# SolarPanelXPlus.net
KiCad netlist of a schematic drawn in Altium Designer
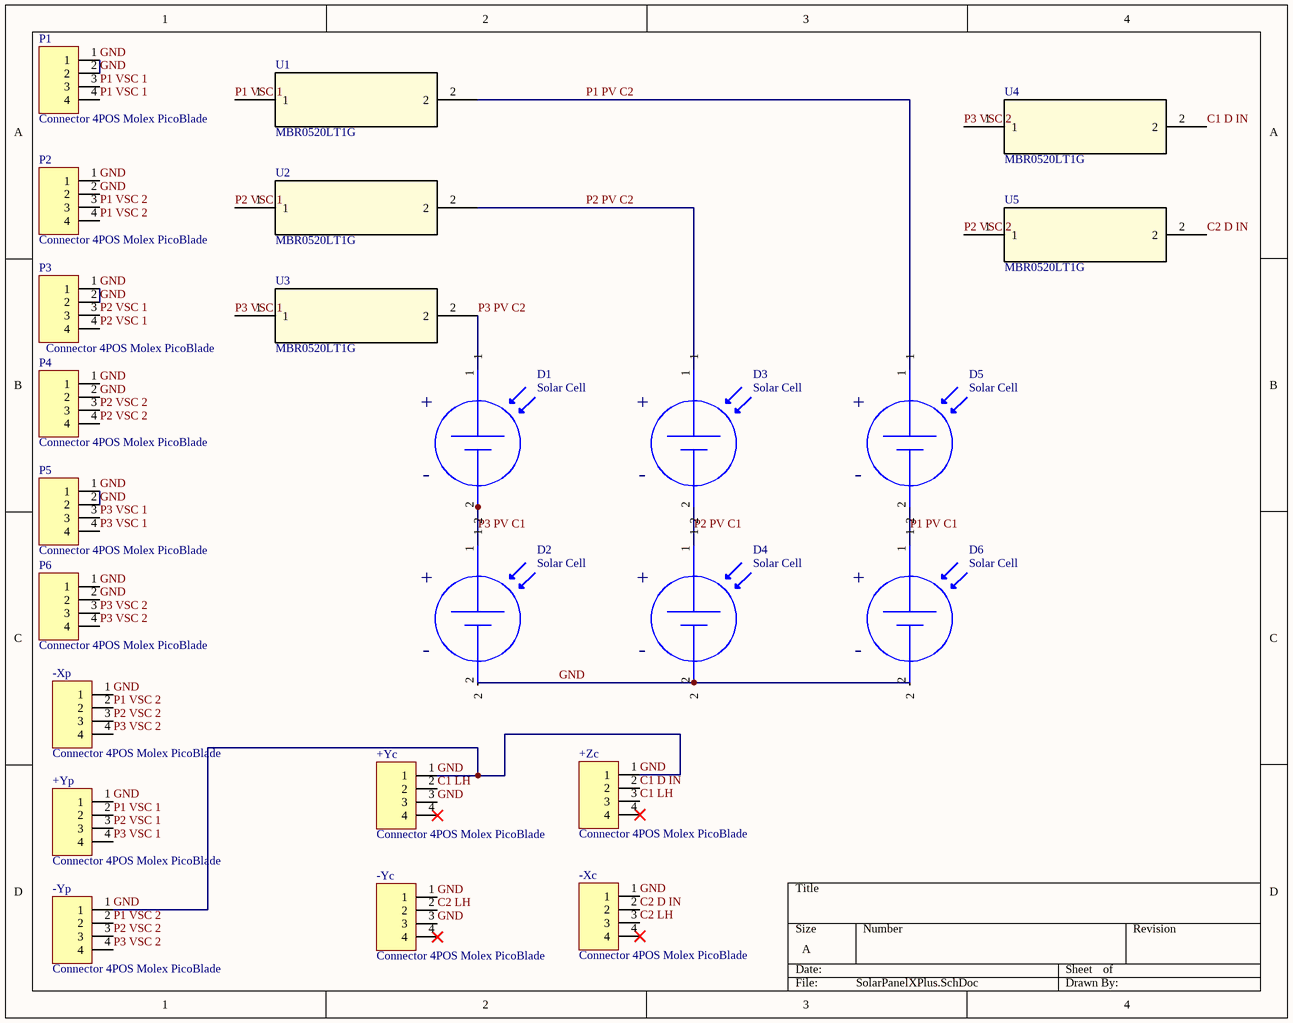
[diagram p0: SolarPanelXPlus.SchDoc]

(export (version "E")
  (design (tool "Eeschema 10.0.6"))
  (components
    (comp (ref "+Yc")
      (value "Connector 4POS Molex PicoBlade")
      (footprint "532610471")
      (libsource (lib "SolarPanelZPlus") (part "532610471"))
    )
    (comp (ref "+Yp")
      (value "Connector 4POS Molex PicoBlade")
      (footprint "532610471")
      (libsource (lib "SolarPanelZPlus") (part "532610471"))
    )
    (comp (ref "+Zc")
      (value "Connector 4POS Molex PicoBlade")
      (footprint "532610471")
      (libsource (lib "SolarPanelZPlus") (part "532610471"))
    )
    (comp (ref "-Xc")
      (value "Connector 4POS Molex PicoBlade")
      (footprint "532610471")
      (libsource (lib "SolarPanelZPlus") (part "532610471"))
    )
    (comp (ref "-Xp")
      (value "Connector 4POS Molex PicoBlade")
      (footprint "532610471")
      (libsource (lib "SolarPanelZPlus") (part "532610471"))
    )
    (comp (ref "-Yc")
      (value "Connector 4POS Molex PicoBlade")
      (footprint "532610471")
      (libsource (lib "SolarPanelZPlus") (part "532610471"))
    )
    (comp (ref "-Yp")
      (value "Connector 4POS Molex PicoBlade")
      (footprint "532610471")
      (libsource (lib "SolarPanelZPlus") (part "532610471"))
    )
    (comp (ref "D1")
      (value "Solar Cell")
      (footprint "SolAeroBJT")
      (description "SolAero BJT Space Solar Cell")
      (libsource (lib "SolarPanelZPlus") (part "SolAeroBJT1"))
    )
    (comp (ref "D2")
      (value "Solar Cell")
      (footprint "SolAeroBJT")
      (description "SolAero BJT Space Solar Cell")
      (libsource (lib "SolarPanelZPlus") (part "SolAeroBJT1"))
    )
    (comp (ref "D3")
      (value "Solar Cell")
      (footprint "SolAeroBJT")
      (description "SolAero BJT Space Solar Cell")
      (libsource (lib "SolarPanelZPlus") (part "SolAeroBJT1"))
    )
    (comp (ref "D4")
      (value "Solar Cell")
      (footprint "SolAeroBJT")
      (description "SolAero BJT Space Solar Cell")
      (libsource (lib "SolarPanelZPlus") (part "SolAeroBJT1"))
    )
    (comp (ref "D5")
      (value "Solar Cell")
      (footprint "SolAeroBJT")
      (description "SolAero BJT Space Solar Cell")
      (libsource (lib "SolarPanelZPlus") (part "SolAeroBJT1"))
    )
    (comp (ref "D6")
      (value "Solar Cell")
      (footprint "SolAeroBJT")
      (description "SolAero BJT Space Solar Cell")
      (libsource (lib "SolarPanelZPlus") (part "SolAeroBJT1"))
    )
    (comp (ref "P1")
      (value "Connector 4POS Molex PicoBlade")
      (footprint "532610471")
      (libsource (lib "SolarPanelZPlus") (part "532610471"))
    )
    (comp (ref "P2")
      (value "Connector 4POS Molex PicoBlade")
      (footprint "532610471")
      (libsource (lib "SolarPanelZPlus") (part "532610471"))
    )
    (comp (ref "P3")
      (value "Connector 4POS Molex PicoBlade")
      (footprint "532610471")
      (libsource (lib "SolarPanelZPlus") (part "532610471"))
    )
    (comp (ref "P4")
      (value "Connector 4POS Molex PicoBlade")
      (footprint "532610471")
      (libsource (lib "SolarPanelZPlus") (part "532610471"))
    )
    (comp (ref "P5")
      (value "Connector 4POS Molex PicoBlade")
      (footprint "532610471")
      (libsource (lib "SolarPanelZPlus") (part "532610471"))
    )
    (comp (ref "P6")
      (value "Connector 4POS Molex PicoBlade")
      (footprint "532610471")
      (libsource (lib "SolarPanelZPlus") (part "532610471"))
    )
    (comp (ref "U1")
      (value "MBR0520LT1G")
      (footprint "SOD-123")
      (description "Imported")
      (fields (field (name "COPYRIGHT") "Copyright (C) 2015 Accelerated Designs. All rights reserved"))
      (libsource (lib "SolarPanelZPlus") (part "MBR0520LT1G"))
    )
    (comp (ref "U2")
      (value "MBR0520LT1G")
      (footprint "SOD-123")
      (description "Imported")
      (fields (field (name "COPYRIGHT") "Copyright (C) 2015 Accelerated Designs. All rights reserved"))
      (libsource (lib "SolarPanelZPlus") (part "MBR0520LT1G"))
    )
    (comp (ref "U3")
      (value "MBR0520LT1G")
      (footprint "SOD-123")
      (description "Imported")
      (fields (field (name "COPYRIGHT") "Copyright (C) 2015 Accelerated Designs. All rights reserved"))
      (libsource (lib "SolarPanelZPlus") (part "MBR0520LT1G"))
    )
    (comp (ref "U4")
      (value "MBR0520LT1G")
      (footprint "SOD-123")
      (description "Imported")
      (fields (field (name "COPYRIGHT") "Copyright (C) 2015 Accelerated Designs. All rights reserved"))
      (libsource (lib "SolarPanelZPlus") (part "MBR0520LT1G"))
    )
    (comp (ref "U5")
      (value "MBR0520LT1G")
      (footprint "SOD-123")
      (description "Imported")
      (fields (field (name "COPYRIGHT") "Copyright (C) 2015 Accelerated Designs. All rights reserved"))
      (libsource (lib "SolarPanelZPlus") (part "MBR0520LT1G"))
    )
  )
  (nets
    (net (code "1") (name "/C1 D IN") (class "Default")
      (node (ref "+Zc") (pin "2") (pinfunction "2_2") (pintype "passive"))
      (node (ref "U4") (pin "2") (pinfunction "2_2") (pintype "passive"))
    )
    (net (code "2") (name "/C1 LH") (class "Default")
      (node (ref "+Yc") (pin "2") (pinfunction "2_2") (pintype "passive"))
      (node (ref "+Zc") (pin "3") (pinfunction "3_3") (pintype "passive"))
    )
    (net (code "3") (name "/C2 D IN") (class "Default")
      (node (ref "-Xc") (pin "2") (pinfunction "2_2") (pintype "passive"))
      (node (ref "U5") (pin "2") (pinfunction "2_2") (pintype "passive"))
    )
    (net (code "4") (name "/C2 LH") (class "Default")
      (node (ref "-Xc") (pin "3") (pinfunction "3_3") (pintype "passive"))
      (node (ref "-Yc") (pin "2") (pinfunction "2_2") (pintype "passive"))
    )
    (net (code "5") (name "/GND") (class "Default")
      (node (ref "+Yc") (pin "1") (pinfunction "1_1") (pintype "passive"))
      (node (ref "+Yc") (pin "3") (pinfunction "3_3") (pintype "passive"))
      (node (ref "+Yp") (pin "1") (pinfunction "1_1") (pintype "passive"))
      (node (ref "+Zc") (pin "1") (pinfunction "1_1") (pintype "passive"))
      (node (ref "-Xc") (pin "1") (pinfunction "1_1") (pintype "passive"))
      (node (ref "-Xp") (pin "1") (pinfunction "1_1") (pintype "passive"))
      (node (ref "-Yc") (pin "1") (pinfunction "1_1") (pintype "passive"))
      (node (ref "-Yc") (pin "3") (pinfunction "3_3") (pintype "passive"))
      (node (ref "-Yp") (pin "1") (pinfunction "1_1") (pintype "passive"))
      (node (ref "D2") (pin "2") (pinfunction "2_2") (pintype "passive"))
      (node (ref "D4") (pin "2") (pinfunction "2_2") (pintype "passive"))
      (node (ref "D6") (pin "2") (pinfunction "2_2") (pintype "passive"))
      (node (ref "P1") (pin "1") (pinfunction "1_1") (pintype "passive"))
      (node (ref "P1") (pin "2") (pinfunction "2_2") (pintype "passive"))
      (node (ref "P2") (pin "1") (pinfunction "1_1") (pintype "passive"))
      (node (ref "P2") (pin "2") (pinfunction "2_2") (pintype "passive"))
      (node (ref "P3") (pin "1") (pinfunction "1_1") (pintype "passive"))
      (node (ref "P3") (pin "2") (pinfunction "2_2") (pintype "passive"))
      (node (ref "P4") (pin "1") (pinfunction "1_1") (pintype "passive"))
      (node (ref "P4") (pin "2") (pinfunction "2_2") (pintype "passive"))
      (node (ref "P5") (pin "1") (pinfunction "1_1") (pintype "passive"))
      (node (ref "P5") (pin "2") (pinfunction "2_2") (pintype "passive"))
      (node (ref "P6") (pin "1") (pinfunction "1_1") (pintype "passive"))
      (node (ref "P6") (pin "2") (pinfunction "2_2") (pintype "passive"))
    )
    (net (code "6") (name "/P1 PV C1") (class "Default")
      (node (ref "D5") (pin "2") (pinfunction "2_2") (pintype "passive"))
      (node (ref "D6") (pin "1") (pinfunction "1_1") (pintype "power_in"))
    )
    (net (code "7") (name "/P1 PV C2") (class "Default")
      (node (ref "D5") (pin "1") (pinfunction "1_1") (pintype "power_in"))
      (node (ref "U1") (pin "2") (pinfunction "2_2") (pintype "passive"))
    )
    (net (code "8") (name "/P1 VSC 1") (class "Default")
      (node (ref "+Yp") (pin "2") (pinfunction "2_2") (pintype "passive"))
      (node (ref "P1") (pin "3") (pinfunction "3_3") (pintype "passive"))
      (node (ref "P1") (pin "4") (pinfunction "4_4") (pintype "passive"))
      (node (ref "U1") (pin "1") (pinfunction "1_1") (pintype "passive"))
    )
    (net (code "9") (name "/P1 VSC 2") (class "Default")
      (node (ref "-Xp") (pin "2") (pinfunction "2_2") (pintype "passive"))
      (node (ref "-Yp") (pin "2") (pinfunction "2_2") (pintype "passive"))
      (node (ref "P2") (pin "3") (pinfunction "3_3") (pintype "passive"))
      (node (ref "P2") (pin "4") (pinfunction "4_4") (pintype "passive"))
    )
    (net (code "10") (name "/P2 PV C1") (class "Default")
      (node (ref "D3") (pin "2") (pinfunction "2_2") (pintype "passive"))
      (node (ref "D4") (pin "1") (pinfunction "1_1") (pintype "power_in"))
    )
    (net (code "11") (name "/P2 PV C2") (class "Default")
      (node (ref "D3") (pin "1") (pinfunction "1_1") (pintype "power_in"))
      (node (ref "U2") (pin "2") (pinfunction "2_2") (pintype "passive"))
    )
    (net (code "12") (name "/P2 VSC 1") (class "Default")
      (node (ref "+Yp") (pin "3") (pinfunction "3_3") (pintype "passive"))
      (node (ref "P3") (pin "3") (pinfunction "3_3") (pintype "passive"))
      (node (ref "P3") (pin "4") (pinfunction "4_4") (pintype "passive"))
      (node (ref "U2") (pin "1") (pinfunction "1_1") (pintype "passive"))
    )
    (net (code "13") (name "/P2 VSC 2") (class "Default")
      (node (ref "-Xp") (pin "3") (pinfunction "3_3") (pintype "passive"))
      (node (ref "-Yp") (pin "3") (pinfunction "3_3") (pintype "passive"))
      (node (ref "P4") (pin "3") (pinfunction "3_3") (pintype "passive"))
      (node (ref "P4") (pin "4") (pinfunction "4_4") (pintype "passive"))
      (node (ref "U5") (pin "1") (pinfunction "1_1") (pintype "passive"))
    )
    (net (code "14") (name "/P3 PV C1") (class "Default")
      (node (ref "D1") (pin "2") (pinfunction "2_2") (pintype "passive"))
      (node (ref "D2") (pin "1") (pinfunction "1_1") (pintype "power_in"))
    )
    (net (code "15") (name "/P3 PV C2") (class "Default")
      (node (ref "D1") (pin "1") (pinfunction "1_1") (pintype "power_in"))
      (node (ref "U3") (pin "2") (pinfunction "2_2") (pintype "passive"))
    )
    (net (code "16") (name "/P3 VSC 1") (class "Default")
      (node (ref "+Yp") (pin "4") (pinfunction "4_4") (pintype "passive"))
      (node (ref "P5") (pin "3") (pinfunction "3_3") (pintype "passive"))
      (node (ref "P5") (pin "4") (pinfunction "4_4") (pintype "passive"))
      (node (ref "U3") (pin "1") (pinfunction "1_1") (pintype "passive"))
    )
    (net (code "17") (name "/P3 VSC 2") (class "Default")
      (node (ref "-Xp") (pin "4") (pinfunction "4_4") (pintype "passive"))
      (node (ref "-Yp") (pin "4") (pinfunction "4_4") (pintype "passive"))
      (node (ref "P6") (pin "3") (pinfunction "3_3") (pintype "passive"))
      (node (ref "P6") (pin "4") (pinfunction "4_4") (pintype "passive"))
      (node (ref "U4") (pin "1") (pinfunction "1_1") (pintype "passive"))
    )
    (net (code "18") (name "unconnected-(+Yc-Pad4)") (class "Default")
      (node (ref "+Yc") (pin "4") (pinfunction "4_4") (pintype "passive+no_connect"))
    )
    (net (code "19") (name "unconnected-(+Zc-Pad4)") (class "Default")
      (node (ref "+Zc") (pin "4") (pinfunction "4_4") (pintype "passive+no_connect"))
    )
    (net (code "20") (name "unconnected-(-Xc-Pad4)") (class "Default")
      (node (ref "-Xc") (pin "4") (pinfunction "4_4") (pintype "passive+no_connect"))
    )
    (net (code "21") (name "unconnected-(-Yc-Pad4)") (class "Default")
      (node (ref "-Yc") (pin "4") (pinfunction "4_4") (pintype "passive+no_connect"))
    )
  )
)
